# Secondary_Protection.net
KiCad netlist of a schematic drawn in Altium Designer
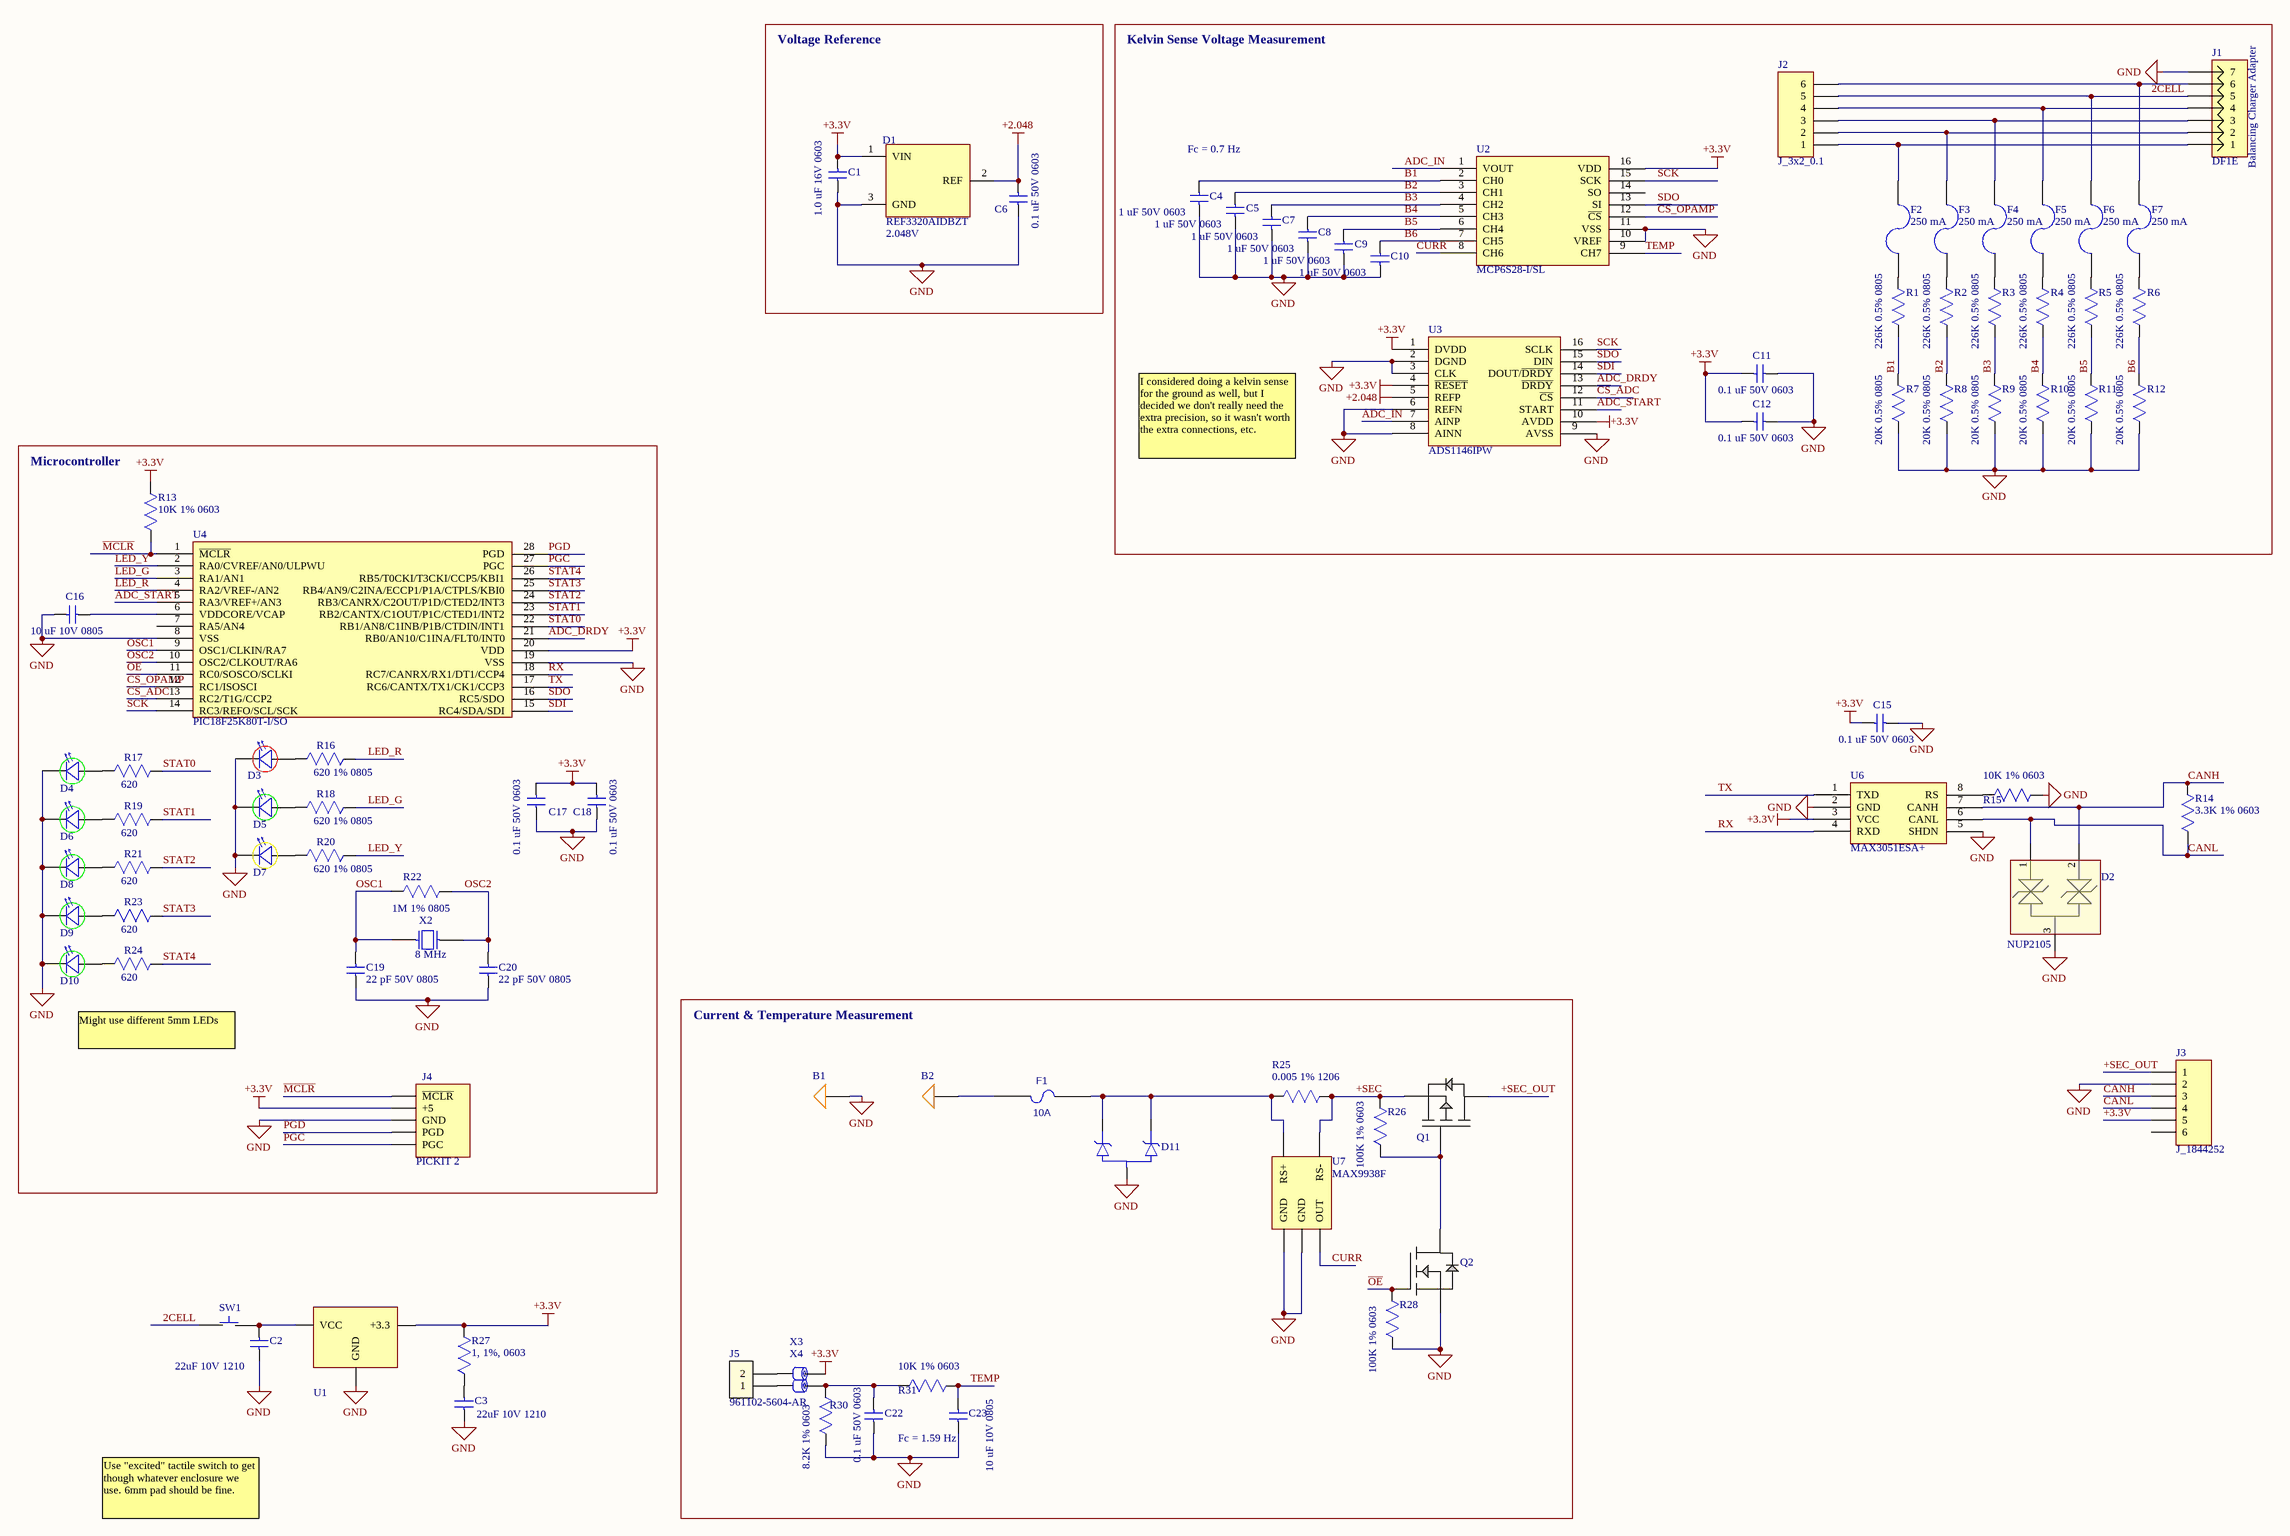
[diagram p0: Secondary Protection.SchDoc]

(export (version "E")
  (design (tool "Eeschema 10.0.6"))
  (components
    (comp (ref "B1")
      (value "J_C3_BATTERY_PAD")
      (footprint "BatteryPad")
      (libsource (lib "c3_SchLib") (part "J_C3_BATTERY_PAD"))
    )
    (comp (ref "B2")
      (value "J_C3_BATTERY_PAD")
      (footprint "BatteryPad")
      (libsource (lib "c3_SchLib") (part "J_C3_BATTERY_PAD"))
    )
    (comp (ref "C1")
      (value "1.0 uF 16V 0603")
      (footprint "0603_cap")
      (description "CAP CER 1UF 16V 10% X7R 0603")
      (fields (field (name "MANUFACTURER") "Taiyo Yuden") (field (name "Comment") "CAP 0603"))
      (libsource (lib "Nutz") (part "C_0603"))
    )
    (comp (ref "C2")
      (value "22uF 10V 1210")
      (footprint "1210_Capacitor")
      (description "CAP CER 22UF 10V 10% X7R 1210")
      (fields (field (name "MANUFACTURER") "TDK Corporation") (field (name "Comment") "CAP 1210"))
      (libsource (lib "c3_SchLib") (part "C_1210"))
    )
    (comp (ref "C3")
      (value "22uF 10V 1210")
      (footprint "1210_Capacitor")
      (description "CAP CER 22UF 10V 10% X7R 1210")
      (fields (field (name "MANUFACTURER") "TDK Corporation") (field (name "Comment") "CAP 1210"))
      (libsource (lib "c3_SchLib") (part "C_1210"))
    )
    (comp (ref "C4")
      (value "1 uF 50V 0603")
      (footprint "0603_cap")
      (description "CAP CER 1UF 50V 10% X7R 0603")
      (fields (field (name "Comment") "CAP 0603"))
      (libsource (lib "Nutz") (part "C_0603"))
    )
    (comp (ref "C5")
      (value "1 uF 50V 0603")
      (footprint "0603_cap")
      (description "CAP CER 1UF 50V 10% X7R 0603")
      (fields (field (name "Comment") "CAP 0603"))
      (libsource (lib "Nutz") (part "C_0603"))
    )
    (comp (ref "C6")
      (value "0.1 uF 50V 0603")
      (footprint "0603_cap")
      (description "CAP CER 0.1UF 50V 10% X7R 0603")
      (fields (field (name "MANUFACTURER") "Yaego") (field (name "Comment") "CAP 0603"))
      (libsource (lib "Nutz") (part "C_0603"))
    )
    (comp (ref "C7")
      (value "1 uF 50V 0603")
      (footprint "0603_cap")
      (description "CAP CER 1UF 50V 10% X7R 0603")
      (fields (field (name "Comment") "CAP 0603"))
      (libsource (lib "Nutz") (part "C_0603"))
    )
    (comp (ref "C8")
      (value "1 uF 50V 0603")
      (footprint "0603_cap")
      (description "CAP CER 1UF 50V 10% X7R 0603")
      (fields (field (name "Comment") "CAP 0603"))
      (libsource (lib "Nutz") (part "C_0603"))
    )
    (comp (ref "C9")
      (value "1 uF 50V 0603")
      (footprint "0603_cap")
      (description "CAP CER 1UF 50V 10% X7R 0603")
      (fields (field (name "Comment") "CAP 0603"))
      (libsource (lib "Nutz") (part "C_0603"))
    )
    (comp (ref "C10")
      (value "1 uF 50V 0603")
      (footprint "0603_cap")
      (description "CAP CER 1UF 50V 10% X7R 0603")
      (fields (field (name "Comment") "CAP 0603"))
      (libsource (lib "Nutz") (part "C_0603"))
    )
    (comp (ref "C11")
      (value "0.1 uF 50V 0603")
      (footprint "0603_cap")
      (description "CAP CER 0.1UF 50V 10% X7R 0603")
      (fields (field (name "MANUFACTURER") "Yaego") (field (name "Comment") "CAP 0603"))
      (libsource (lib "Nutz") (part "C_0603"))
    )
    (comp (ref "C12")
      (value "0.1 uF 50V 0603")
      (footprint "0603_cap")
      (description "CAP CER 0.1UF 50V 10% X7R 0603")
      (fields (field (name "MANUFACTURER") "Yaego") (field (name "Comment") "CAP 0603"))
      (libsource (lib "Nutz") (part "C_0603"))
    )
    (comp (ref "C15")
      (value "0.1 uF 50V 0603")
      (footprint "0603_cap")
      (description "CAP CER 0.1UF 50V 10% X7R 0603")
      (fields (field (name "MANUFACTURER") "Yaego") (field (name "Comment") "CAP 0603"))
      (libsource (lib "Nutz") (part "C_0603"))
    )
    (comp (ref "C16")
      (value "10 uF 10V 0805")
      (footprint "0805_Capacitor")
      (description "CAP CER 10UF 10V 10% X5R 0805")
      (fields (field (name "MANUFACTURER") "Taiyo Yuden") (field (name "Comment") "CAP 0805"))
      (libsource (lib "Nutz") (part "C_0805"))
    )
    (comp (ref "C17")
      (value "0.1 uF 50V 0603")
      (footprint "0603_cap")
      (description "CAP CER 0.1UF 50V 10% X7R 0603")
      (fields (field (name "MANUFACTURER") "Yaego") (field (name "Comment") "CAP 0603"))
      (libsource (lib "Nutz") (part "C_0603"))
    )
    (comp (ref "C18")
      (value "0.1 uF 50V 0603")
      (footprint "0603_cap")
      (description "CAP CER 0.1UF 50V 10% X7R 0603")
      (fields (field (name "MANUFACTURER") "Yaego") (field (name "Comment") "CAP 0603"))
      (libsource (lib "Nutz") (part "C_0603"))
    )
    (comp (ref "C19")
      (value "22 pF 50V 0805")
      (footprint "0805_Capacitor")
      (description "CAP CER 22PF 50V 5% NP0 0805")
      (fields (field (name "MANUFACTURER") "Johanson Dielectrics Inc") (field (name "Comment") "CAP 0805"))
      (libsource (lib "Nutz") (part "C_0805"))
    )
    (comp (ref "C20")
      (value "22 pF 50V 0805")
      (footprint "0805_Capacitor")
      (description "CAP CER 22PF 50V 5% NP0 0805")
      (fields (field (name "MANUFACTURER") "Johanson Dielectrics Inc") (field (name "Comment") "CAP 0805"))
      (libsource (lib "Nutz") (part "C_0805"))
    )
    (comp (ref "C22")
      (value "0.1 uF 50V 0603")
      (footprint "0603_cap")
      (description "CAP CER 0.1UF 50V 10% X7R 0603")
      (fields (field (name "MANUFACTURER") "Yaego") (field (name "Comment") "CAP 0603"))
      (libsource (lib "Nutz") (part "C_0603"))
    )
    (comp (ref "C23")
      (value "10 uF 10V 0805")
      (footprint "0805_Capacitor")
      (description "CAP CER 10UF 10V 10% X5R 0805")
      (fields (field (name "MANUFACTURER") "Taiyo Yuden") (field (name "Comment") "CAP 0805"))
      (libsource (lib "Nutz") (part "C_0805"))
    )
    (comp (ref "D1")
      (value "2.048V")
      (footprint "SOT-23")
      (description "IC LDO V-REF 2.048V SOT23-3")
      (fields (field (name "MANUFACTURER") "TI") (field (name "MANUFACTURER PN") "REF3320AIDBZT"))
      (libsource (lib "c3_SchLib") (part "D_REF3320AIDBZT"))
    )
    (comp (ref "D2")
      (value "CAN TVS")
      (footprint "SOT-23")
      (description "IC CAN BUS PROTECTOR DUAL SOT23")
      (fields (field (name "MANUFACTURER") "ON Semiconductor") (field (name "MANUFACTURER PN") "NUP2105"))
      (libsource (lib "c3_SchLib") (part "D_NUP2105"))
    )
    (comp (ref "D3")
      (value "D_LED_0805_RED")
      (footprint "0805P_RED")
      (description "LED 2X1.2MM 625NM RD WTR CLR SMD 0805")
      (fields (field (name "MANUFACTURER") "Kingbright Corp"))
      (libsource (lib "c3_SchLib") (part "D_LED_0805_RED"))
    )
    (comp (ref "D4")
      (value "D_LED_5MM_GREEN")
      (footprint "LED_5mm_GREEN")
      (description "LED 5MM GREEN CLEAR 527NM 15DEG")
      (fields (field (name "MANUFACTURER") "Cree Inc") (field (name "SVP CREATOR") "Matt Crane"))
      (libsource (lib "c3_SchLib") (part "D_LED_5MM_GREEN"))
    )
    (comp (ref "D5")
      (value "D_LED_0805_GREEN")
      (footprint "0805P_Green")
      (description "LED 2X1.2MM 568NM GN WTR CLR SMD 0805")
      (fields (field (name "MANUFACTURER") "Kingbright Corp"))
      (libsource (lib "c3_SchLib") (part "D_LED_0805_GREEN"))
    )
    (comp (ref "D6")
      (value "D_LED_5MM_GREEN")
      (footprint "LED_5mm_GREEN")
      (description "LED 5MM GREEN CLEAR 527NM 15DEG")
      (fields (field (name "MANUFACTURER") "Cree Inc") (field (name "SVP CREATOR") "Matt Crane"))
      (libsource (lib "c3_SchLib") (part "D_LED_5MM_GREEN"))
    )
    (comp (ref "D7")
      (value "D_LED_0805_YELLOW")
      (footprint "0805P_YELLOW")
      (description "LED 2X1.2MM 588NM YW WTR CLR SMD 0805")
      (fields (field (name "MANUFACTURER") "Kingbright Corp"))
      (libsource (lib "c3_SchLib") (part "D_LED_0805_YELLOW"))
    )
    (comp (ref "D8")
      (value "D_LED_5MM_GREEN")
      (footprint "LED_5mm_GREEN")
      (description "LED 5MM GREEN CLEAR 527NM 15DEG")
      (fields (field (name "MANUFACTURER") "Cree Inc") (field (name "SVP CREATOR") "Matt Crane"))
      (libsource (lib "c3_SchLib") (part "D_LED_5MM_GREEN"))
    )
    (comp (ref "D9")
      (value "D_LED_5MM_GREEN")
      (footprint "LED_5mm_GREEN")
      (description "LED 5MM GREEN CLEAR 527NM 15DEG")
      (fields (field (name "MANUFACTURER") "Cree Inc") (field (name "SVP CREATOR") "Matt Crane"))
      (libsource (lib "c3_SchLib") (part "D_LED_5MM_GREEN"))
    )
    (comp (ref "D10")
      (value "D_LED_5MM_GREEN")
      (footprint "LED_5mm_GREEN")
      (description "LED 5MM GREEN CLEAR 527NM 15DEG")
      (fields (field (name "MANUFACTURER") "Cree Inc") (field (name "SVP CREATOR") "Matt Crane"))
      (libsource (lib "c3_SchLib") (part "D_LED_5MM_GREEN"))
    )
    (comp (ref "D11")
      (value "D_AZ23C36-TP")
      (footprint "SOT-23")
      (description "DIODE ZENER DUAL 36V SOT-23")
      (fields (field (name "MANUFACTURER") "Micro") (field (name "SVP CREATOR") "Jonathan Nutzmann"))
      (libsource (lib "c3_SchLib") (part "D_AZ23C36-TP"))
    )
    (comp (ref "F1")
      (value "10A")
      (footprint "FUSEHOLDER - AutoBlade")
      (description "FUSE HOLDER ATO AUTO BLADE")
      (fields (field (name "PART NUMBER") "3550-2") (field (name "MANUFACTURER") "KEYSTONE/EQUIV."))
      (libsource (lib "G_discrt") (part "FUSEHOLDER AutoBlade"))
    )
    (comp (ref "F2")
      (value "250 mA")
      (footprint "1206_RESISTOR")
      (description "FUSE 250 mA 1206")
      (fields (field (name "SVN CREATOR") "Jonathan Nutzmann") (field (name "SVN REVIEWER 2") "*"))
      (libsource (lib "c3_SchLib") (part "F_250mA_1206"))
    )
    (comp (ref "F3")
      (value "250 mA")
      (footprint "1206_RESISTOR")
      (description "FUSE 250 mA 1206")
      (fields (field (name "SVN CREATOR") "Jonathan Nutzmann") (field (name "SVN REVIEWER 2") "*"))
      (libsource (lib "c3_SchLib") (part "F_250mA_1206"))
    )
    (comp (ref "F4")
      (value "250 mA")
      (footprint "1206_RESISTOR")
      (description "FUSE 250 mA 1206")
      (fields (field (name "SVN CREATOR") "Jonathan Nutzmann") (field (name "SVN REVIEWER 2") "*"))
      (libsource (lib "c3_SchLib") (part "F_250mA_1206"))
    )
    (comp (ref "F5")
      (value "250 mA")
      (footprint "1206_RESISTOR")
      (description "FUSE 250 mA 1206")
      (fields (field (name "SVN CREATOR") "Jonathan Nutzmann") (field (name "SVN REVIEWER 2") "*"))
      (libsource (lib "c3_SchLib") (part "F_250mA_1206"))
    )
    (comp (ref "F6")
      (value "250 mA")
      (footprint "1206_RESISTOR")
      (description "FUSE 250 mA 1206")
      (fields (field (name "SVN CREATOR") "Jonathan Nutzmann") (field (name "SVN REVIEWER 2") "*"))
      (libsource (lib "c3_SchLib") (part "F_250mA_1206"))
    )
    (comp (ref "F7")
      (value "250 mA")
      (footprint "1206_RESISTOR")
      (description "FUSE 250 mA 1206")
      (fields (field (name "SVN CREATOR") "Jonathan Nutzmann") (field (name "SVN REVIEWER 2") "*"))
      (libsource (lib "c3_SchLib") (part "F_250mA_1206"))
    )
    (comp (ref "J1")
      (value "DF1E")
      (footprint "DF1EC-7P-2.5DSA")
      (description "7-pin Hirose")
      (fields
        (field (name "MANUFACTURER") "Hirose Electric Co Ltd")
        (field (name "Comment") "DF1E 5-pin Male Header")
        (field (name "SVP CREATOR") "Adam Shea")
      )
      (libsource (lib "Hirose") (part "DF1E_7_S"))
    )
    (comp (ref "J2")
      (value "J_3x2_0.1")
      (footprint "6PIN_2_.100IN")
      (description "3 x 2 0.1\" Header")
      (libsource (lib "Nutz") (part "J_3x2_0.1"))
    )
    (comp (ref "J3")
      (value "J_1844252")
      (footprint "1844252")
      (description "CONN HEADER RT ANG 6POS 3.5MM")
      (fields (field (name "MANUFACTURER") "Phoenix Contact"))
      (libsource (lib "Nutz") (part "J_1803316"))
    )
    (comp (ref "J4")
      (value "PICKIT 2")
      (footprint "CONN FEMALE 5POS .100\" R/A GOLD")
      (description "PICKIT2 PROG HEADER")
      (fields
        (field (name "MANUFACTURER") "Sullins Connector Solutions")
        (field (name "Comment") "J_PICKIT2_5")
      )
      (libsource (lib "c3_SchLib") (part "J_PICKIT2_5"))
    )
    (comp (ref "J5")
      (value "J_Thermistor_Connector")
      (footprint "SIP_HEADER_2")
      (description "Thermistor Connector")
      (fields (field (name "MANUFACTURER PN") "961102-5604-AR") (field (name "MANUFACTURER") "3M"))
      (libsource (lib "c3_SchLib") (part "J_Thermistor_Connector"))
    )
    (comp (ref "Q1")
      (value "MOSFET P-CH 30V 25A TO-252")
      (footprint "DPAK")
      (description "MOSFET P-CH 30V 25A TO-252 DPAK")
      (fields
        (field (name "MANUFACTURER") "Alpha & Omega Semiconductor Inc")
        (field (name "SVP CREATOR") "Brittany Pentek")
        (field (name "SVP REVIEWER 1") "Brett Paulsen")
      )
      (libsource (lib "c3_SchLib") (part "Q_AOD417_ P-CH_-30A_-25A_DPAK"))
    )
    (comp (ref "Q2")
      (value "RK7002BT116")
      (footprint "SOT-23")
      (description "MOSFET N-CH 60V 250MA SOT-23")
      (fields
        (field (name "MANUFACTURER") "Rohm Semiconductor")
        (field (name "SVP CREATOR") "Jonathan Nutzmann")
      )
      (libsource (lib "c3_SchLib") (part "Q_N_60V_250MA_SOT23"))
    )
    (comp (ref "R1")
      (value "226K 0.5% 0805")
      (footprint "0805_Resistor")
      (description "RESISTOR, 1/10W, 226K, 0.5%, 0805")
      (fields (field (name "MANUFACTURER") "Susumu") (field (name "Comment") "RES 0805"))
      (libsource (lib "Nutz") (part "R_0805"))
    )
    (comp (ref "R2")
      (value "226K 0.5% 0805")
      (footprint "0805_Resistor")
      (description "RESISTOR, 1/10W, 226K, 0.5%, 0805")
      (fields (field (name "MANUFACTURER") "Susumu") (field (name "Comment") "RES 0805"))
      (libsource (lib "Nutz") (part "R_0805"))
    )
    (comp (ref "R3")
      (value "226K 0.5% 0805")
      (footprint "0805_Resistor")
      (description "RESISTOR, 1/10W, 226K, 0.5%, 0805")
      (fields (field (name "MANUFACTURER") "Susumu") (field (name "Comment") "RES 0805"))
      (libsource (lib "Nutz") (part "R_0805"))
    )
    (comp (ref "R4")
      (value "226K 0.5% 0805")
      (footprint "0805_Resistor")
      (description "RESISTOR, 1/10W, 226K, 0.5%, 0805")
      (fields (field (name "MANUFACTURER") "Susumu") (field (name "Comment") "RES 0805"))
      (libsource (lib "Nutz") (part "R_0805"))
    )
    (comp (ref "R5")
      (value "226K 0.5% 0805")
      (footprint "0805_Resistor")
      (description "RESISTOR, 1/10W, 226K, 0.5%, 0805")
      (fields (field (name "MANUFACTURER") "Susumu") (field (name "Comment") "RES 0805"))
      (libsource (lib "Nutz") (part "R_0805"))
    )
    (comp (ref "R6")
      (value "226K 0.5% 0805")
      (footprint "0805_Resistor")
      (description "RESISTOR, 1/10W, 226K, 0.5%, 0805")
      (fields (field (name "MANUFACTURER") "Susumu") (field (name "Comment") "RES 0805"))
      (libsource (lib "Nutz") (part "R_0805"))
    )
    (comp (ref "R7")
      (value "20K 0.5% 0805")
      (footprint "0805_Resistor")
      (description "RESISTOR, 1/10W, 20K, 0.5%, 0805")
      (fields (field (name "MANUFACTURER") "Susumu") (field (name "Comment") "RES 0805"))
      (libsource (lib "Nutz") (part "R_0805"))
    )
    (comp (ref "R8")
      (value "20K 0.5% 0805")
      (footprint "0805_Resistor")
      (description "RESISTOR, 1/10W, 20K, 0.5%, 0805")
      (fields (field (name "MANUFACTURER") "Susumu") (field (name "Comment") "RES 0805"))
      (libsource (lib "Nutz") (part "R_0805"))
    )
    (comp (ref "R9")
      (value "20K 0.5% 0805")
      (footprint "0805_Resistor")
      (description "RESISTOR, 1/10W, 20K, 0.5%, 0805")
      (fields (field (name "MANUFACTURER") "Susumu") (field (name "Comment") "RES 0805"))
      (libsource (lib "Nutz") (part "R_0805"))
    )
    (comp (ref "R10")
      (value "20K 0.5% 0805")
      (footprint "0805_Resistor")
      (description "RESISTOR, 1/10W, 20K, 0.5%, 0805")
      (fields (field (name "MANUFACTURER") "Susumu") (field (name "Comment") "RES 0805"))
      (libsource (lib "Nutz") (part "R_0805"))
    )
    (comp (ref "R11")
      (value "20K 0.5% 0805")
      (footprint "0805_Resistor")
      (description "RESISTOR, 1/10W, 20K, 0.5%, 0805")
      (fields (field (name "MANUFACTURER") "Susumu") (field (name "Comment") "RES 0805"))
      (libsource (lib "Nutz") (part "R_0805"))
    )
    (comp (ref "R12")
      (value "20K 0.5% 0805")
      (footprint "0805_Resistor")
      (description "RESISTOR, 1/10W, 20K, 0.5%, 0805")
      (fields (field (name "MANUFACTURER") "Susumu") (field (name "Comment") "RES 0805"))
      (libsource (lib "Nutz") (part "R_0805"))
    )
    (comp (ref "R13")
      (value "10K 1% 0603")
      (footprint "0603_res")
      (description "RESISTOR, 1/10W, 10K, 1%, 0603")
      (fields (field (name "MANUFACTURER") "ANY / EQUIV") (field (name "Comment") "RES 0603"))
      (libsource (lib "Nutz") (part "R_0603"))
    )
    (comp (ref "R14")
      (value "3.3K 1% 0603")
      (footprint "0603_res")
      (description "RESISTOR, 1/10W, 3.3K, 1%, 0603")
      (fields (field (name "MANUFACTURER") "ANY / EQUIV") (field (name "Comment") "RES 0603"))
      (libsource (lib "Nutz") (part "R_0603"))
    )
    (comp (ref "R15")
      (value "10K 1% 0603")
      (footprint "0603_res")
      (description "RESISTOR, 1/10W, 10K, 1%, 0603")
      (fields (field (name "MANUFACTURER") "ANY / EQUIV") (field (name "Comment") "RES 0603"))
      (libsource (lib "Nutz") (part "R_0603"))
    )
    (comp (ref "R16")
      (value "620 1% 0805")
      (footprint "0805_Resistor")
      (description "RESISTOR, 1/8W, 620, 1%, 0805")
      (fields (field (name "MANUFACTURER") "ANY / EQUIV") (field (name "Comment") "R_0805_620_1%"))
      (libsource (lib "c3_SchLib") (part "R_0805_620_1%"))
    )
    (comp (ref "R17")
      (value "620")
      (footprint "0805_Resistor")
      (description "RES 620 OHM 1/8W 1% 0805 SMD")
      (fields (field (name "Comment") "R_0805_620_1%") (field (name "SVP CREATOR") "Jonathan Nutzmann"))
      (libsource (lib "c3_SchLib") (part "R_0805_620_1%"))
    )
    (comp (ref "R18")
      (value "620 1% 0805")
      (footprint "0805_Resistor")
      (description "RESISTOR, 1/8W, 620, 1%, 0805")
      (fields (field (name "MANUFACTURER") "ANY / EQUIV") (field (name "Comment") "R_0805_620_1%"))
      (libsource (lib "c3_SchLib") (part "R_0805_620_1%"))
    )
    (comp (ref "R19")
      (value "620")
      (footprint "0805_Resistor")
      (description "RES 620 OHM 1/8W 1% 0805 SMD")
      (fields (field (name "Comment") "R_0805_620_1%") (field (name "SVP CREATOR") "Jonathan Nutzmann"))
      (libsource (lib "c3_SchLib") (part "R_0805_620_1%"))
    )
    (comp (ref "R20")
      (value "620 1% 0805")
      (footprint "0805_Resistor")
      (description "RESISTOR, 1/8W, 620, 1%, 0805")
      (fields (field (name "MANUFACTURER") "ANY / EQUIV") (field (name "Comment") "R_0805_620_1%"))
      (libsource (lib "c3_SchLib") (part "R_0805_620_1%"))
    )
    (comp (ref "R21")
      (value "620")
      (footprint "0805_Resistor")
      (description "RES 620 OHM 1/8W 1% 0805 SMD")
      (fields (field (name "Comment") "R_0805_620_1%") (field (name "SVP CREATOR") "Jonathan Nutzmann"))
      (libsource (lib "c3_SchLib") (part "R_0805_620_1%"))
    )
    (comp (ref "R22")
      (value "1M 1% 0805")
      (footprint "0805_Resistor")
      (description "RESISTOR, 1/8W, 1M, 1%, 0805")
      (fields (field (name "MANUFACTURER") "ANY / EQUIV") (field (name "Comment") "RES 0805"))
      (libsource (lib "Nutz") (part "R_0805"))
    )
    (comp (ref "R23")
      (value "620")
      (footprint "0805_Resistor")
      (description "RES 620 OHM 1/8W 1% 0805 SMD")
      (fields (field (name "Comment") "R_0805_620_1%") (field (name "SVP CREATOR") "Jonathan Nutzmann"))
      (libsource (lib "c3_SchLib") (part "R_0805_620_1%"))
    )
    (comp (ref "R24")
      (value "620")
      (footprint "0805_Resistor")
      (description "RES 620 OHM 1/8W 1% 0805 SMD")
      (fields (field (name "Comment") "R_0805_620_1%") (field (name "SVP CREATOR") "Jonathan Nutzmann"))
      (libsource (lib "c3_SchLib") (part "R_0805_620_1%"))
    )
    (comp (ref "R25")
      (value "0.005 1% 1206")
      (footprint "1206_Resistor")
      (description "RES CURRENT SENSE .005 OHM 1W 1%")
      (fields (field (name "MANUFACTURER") "MCS1632R010FER") (field (name "Comment") "R_0805_0.01_1%"))
      (libsource (lib "c3_SchLib") (part "R_0805_0.01_1%"))
    )
    (comp (ref "R26")
      (value "100K 1% 0603")
      (footprint "0603_res")
      (description "RESISTOR, 1/10W, 500K, 1%, 0603")
      (fields (field (name "MANUFACTURER") "ANY / EQUIV") (field (name "Comment") "RES 0603"))
      (libsource (lib "Nutz") (part "R_0603"))
    )
    (comp (ref "R27")
      (value "1, 1%, 0603")
      (footprint "0603_res")
      (description "RES 0603")
      (libsource (lib "Nutz") (part "R_0603"))
    )
    (comp (ref "R28")
      (value "100K 1% 0603")
      (footprint "0603_res")
      (description "RESISTOR, 1/10W, 500K, 1%, 0603")
      (fields (field (name "MANUFACTURER") "ANY / EQUIV") (field (name "Comment") "RES 0603"))
      (libsource (lib "Nutz") (part "R_0603"))
    )
    (comp (ref "R30")
      (value "8.2K 1% 0603")
      (footprint "0603_res")
      (description "RESISTOR, 1/10W, 8.2K, 1%, 0603")
      (fields (field (name "MANUFACTURER") "ANY / EQUIV") (field (name "Comment") "RES 0603"))
      (libsource (lib "Nutz") (part "R_0603"))
    )
    (comp (ref "R31")
      (value "10K 1% 0603")
      (footprint "0603_res")
      (description "RESISTOR, 1/10W, 10K, 1%, 0603")
      (fields (field (name "MANUFACTURER") "ANY / EQUIV") (field (name "Comment") "RES 0603"))
      (libsource (lib "Nutz") (part "R_0603"))
    )
    (comp (ref "SW1")
      (value "SW_TACT_SWITCH_6x6")
      (footprint "TACT_SWITCH_6x6")
      (description "SWITCH TACT 6MM BLACK 160GF")
      (fields (field (name "MANUFACTURER") "Tyco Electronics") (field (name "SVP CREATOR") "Nate Bolyard"))
      (libsource (lib "Noprotection") (part "SW_TACT_SWITCH_6x6"))
    )
    (comp (ref "U1")
      (value "MC7805BDTG")
      (footprint "DPAK")
      (description "IC REG LDO BIPO 1A 3.3V TO252-3")
      (fields (field (name "MANUFACTURER") "Diodes Inc") (field (name "SVP CREATOR") "Thomas Daede"))
      (libsource (lib "c3_SchLib") (part "U_AP1117D33G_1"))
    )
    (comp (ref "U2")
      (value "U_MCP6S28-I/SL")
      (footprint "SOIC127P600X175-16N")
      (description "IC PGA 8CH R-R I/O 16SOIC")
      (fields (field (name "MANUFACTURER") "Microchip") (field (name "MANUFACTURER PN") "MCP6S28-I/SL"))
      (libsource (lib "Nutz") (part "U_MCP6S28-I/SL"))
    )
    (comp (ref "U3")
      (value "U_ADS1146IPW")
      (footprint "ADS1146IPW")
      (description "IC ADC 16BIT SRL 2KSPS 16TSSOP")
      (fields (field (name "MANUFACTURER") "Texas Instruments") (field (name "MANUFACTURER PN") "ADS1146IPW"))
      (libsource (lib "Nutz") (part "U_ADS1146IPW"))
    )
    (comp (ref "U4")
      (value "PIC18F25K80")
      (footprint "SOIC127P1030X265-28N")
      (description "MCU PIC 32KB FLASH 28SOIC")
      (fields (field (name "MANUFACTURER") "Microchip") (field (name "MANUFACTURER PN") "PIC18F25K80T-I/SO"))
      (libsource (lib "c3_SchLib") (part "U_PIC18F25K80"))
    )
    (comp (ref "U6")
      (value "U_MAX3051")
      (footprint "SOIC127P600X175-8N")
      (description "IC TXRX CAN 1MBPS 8-SOIC 3.3V")
      (fields (field (name "MANUFACTURER") "Maxim") (field (name "MANUFACTURER PN") "MAX3051ESA+"))
      (libsource (lib "c3_SchLib") (part "U_MAX3051"))
    )
    (comp (ref "U7")
      (value "MAX9938F")
      (footprint "SOT95P280X145-5N")
      (description "IC AMP CURRENT SENSE SOT23-5")
      (fields (field (name "MANUFACTURER") "Maxim") (field (name "Comment") "U_ MAX9938F"))
      (libsource (lib "c3_SchLib") (part "U_ MAX9938F"))
    )
    (comp (ref "X2")
      (value "8 MHz")
      (footprint "HC-49")
      (description "CRYSTAL 8.00 MHZ 20PF 49US")
      (fields (field (name "MANUFACTURER") "ECS") (field (name "Comment") "HC49"))
      (libsource (lib "c3_SchLib") (part "X_HC49"))
    )
    (comp (ref "X3")
      (value "0603")
      (footprint "0603_res")
      (description "FERRITE CHIP 2A 300 OHM SMD")
      (fields (field (name "MANUFACTURER") "Laird-Signal Integrity Products"))
      (libsource (lib "Nutz") (part "X_0603_FERRITE"))
    )
    (comp (ref "X4")
      (value "0603")
      (footprint "0603_res")
      (description "FERRITE CHIP 2A 300 OHM SMD")
      (fields (field (name "MANUFACTURER") "Laird-Signal Integrity Products"))
      (libsource (lib "Nutz") (part "X_0603_FERRITE"))
    )
  )
  (nets
    (net (code "1") (name "+2.048") (class "Default")
      (node (ref "C6") (pin "1") (pinfunction "1_1") (pintype "passive"))
      (node (ref "D1") (pin "2") (pinfunction "REF_2") (pintype "passive"))
      (node (ref "U3") (pin "5") (pinfunction "REFP_5") (pintype "passive"))
    )
    (net (code "2") (name "+3.3V") (class "Default")
      (node (ref "C1") (pin "1") (pinfunction "1_1") (pintype "passive"))
      (node (ref "C11") (pin "2") (pinfunction "2_2") (pintype "passive"))
      (node (ref "C12") (pin "2") (pinfunction "2_2") (pintype "passive"))
      (node (ref "C15") (pin "1") (pinfunction "1_1") (pintype "passive"))
      (node (ref "C17") (pin "1") (pinfunction "1_1") (pintype "passive"))
      (node (ref "C18") (pin "1") (pinfunction "1_1") (pintype "passive"))
      (node (ref "D1") (pin "1") (pinfunction "VIN_1") (pintype "passive"))
      (node (ref "J3") (pin "5") (pinfunction "5_5") (pintype "passive"))
      (node (ref "J4") (pin "+5") (pinfunction "+5_+5") (pintype "passive"))
      (node (ref "R13") (pin "1") (pinfunction "1_1") (pintype "passive"))
      (node (ref "R27") (pin "1") (pinfunction "1_1") (pintype "passive"))
      (node (ref "U1") (pin "1") (pinfunction "+3.3_1") (pintype "passive"))
      (node (ref "U2") (pin "16") (pinfunction "VDD_16") (pintype "passive"))
      (node (ref "U3") (pin "1") (pinfunction "DVDD_1") (pintype "passive"))
      (node (ref "U3") (pin "10") (pinfunction "AVDD_10") (pintype "passive"))
      (node (ref "U3") (pin "4") (pinfunction "~{RESET}_4") (pintype "passive"))
      (node (ref "U4") (pin "20") (pinfunction "VDD_20") (pintype "passive"))
      (node (ref "U6") (pin "3") (pinfunction "VCC_3") (pintype "passive"))
      (node (ref "X3") (pin "2") (pinfunction "2_2") (pintype "passive"))
    )
    (net (code "3") (name "/+SEC") (class "Default")
      (node (ref "Q1") (pin "2") (pinfunction "SOURCE_2") (pintype "passive"))
      (node (ref "R25") (pin "1") (pinfunction "1_1") (pintype "passive"))
      (node (ref "R26") (pin "1") (pinfunction "1_1") (pintype "passive"))
      (node (ref "U7") (pin "4") (pinfunction "RS-_4") (pintype "passive"))
    )
    (net (code "4") (name "/+SEC_OUT") (class "Default")
      (node (ref "J3") (pin "1") (pinfunction "1_1") (pintype "passive"))
      (node (ref "Q1") (pin "1") (pinfunction "DRAIN_1") (pintype "passive"))
    )
    (net (code "5") (name "/2CELL") (class "Default")
      (node (ref "F6") (pin "2") (pinfunction "2_2") (pintype "passive"))
      (node (ref "J1") (pin "5") (pinfunction "5_5") (pintype "passive"))
      (node (ref "J2") (pin "5") (pinfunction "5_5") (pintype "passive"))
      (node (ref "SW1") (pin "1") (pinfunction "1_1") (pintype "passive"))
    )
    (net (code "6") (name "/ADC_DRDY") (class "Default")
      (node (ref "U3") (pin "13") (pinfunction "~{DRDY}_13") (pintype "passive"))
      (node (ref "U4") (pin "21") (pinfunction "RB0/AN10/C1INA/FLT0/INT0_21") (pintype "passive"))
    )
    (net (code "7") (name "/ADC_IN") (class "Default")
      (node (ref "U2") (pin "1") (pinfunction "VOUT_1") (pintype "passive"))
      (node (ref "U3") (pin "7") (pinfunction "AINP_7") (pintype "passive"))
    )
    (net (code "8") (name "/ADC_START") (class "Default")
      (node (ref "U3") (pin "11") (pinfunction "START_11") (pintype "passive"))
      (node (ref "U4") (pin "5") (pinfunction "RA3/VREF+/AN3_5") (pintype "passive"))
    )
    (net (code "9") (name "/B1") (class "Default")
      (node (ref "C4") (pin "2") (pinfunction "2_2") (pintype "passive"))
      (node (ref "R1") (pin "2") (pinfunction "2_2") (pintype "passive"))
      (node (ref "R7") (pin "1") (pinfunction "1_1") (pintype "passive"))
      (node (ref "U2") (pin "2") (pinfunction "CH0_2") (pintype "passive"))
    )
    (net (code "10") (name "/B2") (class "Default")
      (node (ref "C5") (pin "2") (pinfunction "2_2") (pintype "passive"))
      (node (ref "R2") (pin "2") (pinfunction "2_2") (pintype "passive"))
      (node (ref "R8") (pin "1") (pinfunction "1_1") (pintype "passive"))
      (node (ref "U2") (pin "3") (pinfunction "CH1_3") (pintype "passive"))
    )
    (net (code "11") (name "/B3") (class "Default")
      (node (ref "C7") (pin "2") (pinfunction "2_2") (pintype "passive"))
      (node (ref "R3") (pin "2") (pinfunction "2_2") (pintype "passive"))
      (node (ref "R9") (pin "1") (pinfunction "1_1") (pintype "passive"))
      (node (ref "U2") (pin "4") (pinfunction "CH2_4") (pintype "passive"))
    )
    (net (code "12") (name "/B4") (class "Default")
      (node (ref "C8") (pin "2") (pinfunction "2_2") (pintype "passive"))
      (node (ref "R10") (pin "1") (pinfunction "1_1") (pintype "passive"))
      (node (ref "R4") (pin "2") (pinfunction "2_2") (pintype "passive"))
      (node (ref "U2") (pin "5") (pinfunction "CH3_5") (pintype "passive"))
    )
    (net (code "13") (name "/B5") (class "Default")
      (node (ref "C9") (pin "2") (pinfunction "2_2") (pintype "passive"))
      (node (ref "R11") (pin "1") (pinfunction "1_1") (pintype "passive"))
      (node (ref "R5") (pin "2") (pinfunction "2_2") (pintype "passive"))
      (node (ref "U2") (pin "6") (pinfunction "CH4_6") (pintype "passive"))
    )
    (net (code "14") (name "/B6") (class "Default")
      (node (ref "C10") (pin "2") (pinfunction "2_2") (pintype "passive"))
      (node (ref "R12") (pin "1") (pinfunction "1_1") (pintype "passive"))
      (node (ref "R6") (pin "2") (pinfunction "2_2") (pintype "passive"))
      (node (ref "U2") (pin "7") (pinfunction "CH5_7") (pintype "passive"))
    )
    (net (code "15") (name "/CANH") (class "Default")
      (node (ref "D2") (pin "2") (pintype "passive"))
      (node (ref "J3") (pin "3") (pinfunction "3_3") (pintype "passive"))
      (node (ref "R14") (pin "1") (pinfunction "1_1") (pintype "passive"))
      (node (ref "U6") (pin "7") (pinfunction "CANH_7") (pintype "passive"))
    )
    (net (code "16") (name "/CANL") (class "Default")
      (node (ref "D2") (pin "1") (pintype "passive"))
      (node (ref "J3") (pin "4") (pinfunction "4_4") (pintype "passive"))
      (node (ref "R14") (pin "2") (pinfunction "2_2") (pintype "passive"))
      (node (ref "U6") (pin "6") (pinfunction "CANL_6") (pintype "passive"))
    )
    (net (code "17") (name "/CURR") (class "Default")
      (node (ref "U2") (pin "8") (pinfunction "CH6_8") (pintype "passive"))
      (node (ref "U7") (pin "3") (pinfunction "OUT_3") (pintype "passive"))
    )
    (net (code "18") (name "/LED_G") (class "Default")
      (node (ref "R18") (pin "1") (pinfunction "1_1") (pintype "passive"))
      (node (ref "U4") (pin "3") (pinfunction "RA1/AN1_3") (pintype "passive"))
    )
    (net (code "19") (name "/LED_R") (class "Default")
      (node (ref "R16") (pin "1") (pinfunction "1_1") (pintype "passive"))
      (node (ref "U4") (pin "4") (pinfunction "RA2/VREF-/AN2_4") (pintype "passive"))
    )
    (net (code "20") (name "/LED_Y") (class "Default")
      (node (ref "R20") (pin "1") (pinfunction "1_1") (pintype "passive"))
      (node (ref "U4") (pin "2") (pinfunction "RA0/CVREF/AN0/ULPWU_2") (pintype "passive"))
    )
    (net (code "21") (name "/OSC1") (class "Default")
      (node (ref "C19") (pin "1") (pinfunction "1_1") (pintype "passive"))
      (node (ref "R22") (pin "2") (pinfunction "2_2") (pintype "passive"))
      (node (ref "U4") (pin "9") (pinfunction "OSC1/CLKIN/RA7_9") (pintype "passive"))
      (node (ref "X2") (pin "2") (pinfunction "2_2") (pintype "passive"))
    )
    (net (code "22") (name "/OSC2") (class "Default")
      (node (ref "C20") (pin "1") (pinfunction "1_1") (pintype "passive"))
      (node (ref "R22") (pin "1") (pinfunction "1_1") (pintype "passive"))
      (node (ref "U4") (pin "10") (pinfunction "OSC2/CLKOUT/RA6_10") (pintype "passive"))
      (node (ref "X2") (pin "1") (pinfunction "1_1") (pintype "passive"))
    )
    (net (code "23") (name "/PGC") (class "Default")
      (node (ref "J4") (pin "PGC") (pinfunction "PGC_PGC") (pintype "passive"))
      (node (ref "U4") (pin "27") (pinfunction "PGC_27") (pintype "passive"))
    )
    (net (code "24") (name "/PGD") (class "Default")
      (node (ref "J4") (pin "PGD") (pinfunction "PGD_PGD") (pintype "passive"))
      (node (ref "U4") (pin "28") (pinfunction "PGD_28") (pintype "passive"))
    )
    (net (code "25") (name "/RX") (class "Default")
      (node (ref "U4") (pin "18") (pinfunction "RC7/CANRX/RX1/DT1/CCP4_18") (pintype "passive"))
      (node (ref "U6") (pin "4") (pinfunction "RXD_4") (pintype "passive"))
    )
    (net (code "26") (name "/SCK") (class "Default")
      (node (ref "U2") (pin "15") (pinfunction "SCK_15") (pintype "passive"))
      (node (ref "U3") (pin "16") (pinfunction "SCLK_16") (pintype "passive"))
      (node (ref "U4") (pin "14") (pinfunction "RC3/REFO/SCL/SCK_14") (pintype "passive"))
    )
    (net (code "27") (name "/SDI") (class "Default")
      (node (ref "U3") (pin "14") (pinfunction "DOUT/~{DRDY}_14") (pintype "passive"))
      (node (ref "U4") (pin "15") (pinfunction "RC4/SDA/SDI_15") (pintype "passive"))
    )
    (net (code "28") (name "/SDO") (class "Default")
      (node (ref "U2") (pin "13") (pinfunction "SI_13") (pintype "passive"))
      (node (ref "U3") (pin "15") (pinfunction "DIN_15") (pintype "passive"))
      (node (ref "U4") (pin "16") (pinfunction "RC5/SDO_16") (pintype "passive"))
    )
    (net (code "29") (name "/STAT0") (class "Default")
      (node (ref "R17") (pin "1") (pinfunction "1_1") (pintype "passive"))
      (node (ref "U4") (pin "22") (pinfunction "RB1/AN8/C1INB/P1B/CTDIN/INT1_22") (pintype "passive"))
    )
    (net (code "30") (name "/STAT1") (class "Default")
      (node (ref "R19") (pin "1") (pinfunction "1_1") (pintype "passive"))
      (node (ref "U4") (pin "23") (pinfunction "RB2/CANTX/C1OUT/P1C/CTED1/INT2_23") (pintype "passive"))
    )
    (net (code "31") (name "/STAT2") (class "Default")
      (node (ref "R21") (pin "1") (pinfunction "1_1") (pintype "passive"))
      (node (ref "U4") (pin "24") (pinfunction "RB3/CANRX/C2OUT/P1D/CTED2/INT3_24") (pintype "passive"))
    )
    (net (code "32") (name "/STAT3") (class "Default")
      (node (ref "R23") (pin "1") (pinfunction "1_1") (pintype "passive"))
      (node (ref "U4") (pin "25") (pinfunction "RB4/AN9/C2INA/ECCP1/P1A/CTPLS/KBI0_25") (pintype "passive"))
    )
    (net (code "33") (name "/STAT4") (class "Default")
      (node (ref "R24") (pin "1") (pinfunction "1_1") (pintype "passive"))
      (node (ref "U4") (pin "26") (pinfunction "RB5/T0CKI/T3CKI/CCP5/KBI1_26") (pintype "passive"))
    )
    (net (code "34") (name "/TEMP") (class "Default")
      (node (ref "C23") (pin "1") (pinfunction "1_1") (pintype "passive"))
      (node (ref "R31") (pin "1") (pinfunction "1_1") (pintype "passive"))
      (node (ref "U2") (pin "9") (pinfunction "CH7_9") (pintype "passive"))
    )
    (net (code "35") (name "/TX") (class "Default")
      (node (ref "U4") (pin "17") (pinfunction "RC6/CANTX/TX1/CK1/CCP3_17") (pintype "passive"))
      (node (ref "U6") (pin "1") (pinfunction "TXD_1") (pintype "passive"))
    )
    (net (code "36") (name "/~{CS}_ADC") (class "Default")
      (node (ref "U3") (pin "12") (pinfunction "~{CS}_12") (pintype "passive"))
      (node (ref "U4") (pin "13") (pinfunction "RC2/T1G/CCP2_13") (pintype "passive"))
    )
    (net (code "37") (name "/~{CS}_OPAMP") (class "Default")
      (node (ref "U2") (pin "12") (pinfunction "~{CS}_12") (pintype "passive"))
      (node (ref "U4") (pin "12") (pinfunction "RC1/ISOSCI_12") (pintype "passive"))
    )
    (net (code "38") (name "/~{MCLR}") (class "Default")
      (node (ref "J4") (pin "RST") (pinfunction "~{MCLR}_RST") (pintype "passive"))
      (node (ref "R13") (pin "2") (pinfunction "2_2") (pintype "passive"))
      (node (ref "U4") (pin "1") (pinfunction "~{MCLR}_1") (pintype "passive"))
    )
    (net (code "39") (name "/~{OE}") (class "Default")
      (node (ref "Q2") (pin "1") (pinfunction "GATE_1") (pintype "passive"))
      (node (ref "R28") (pin "1") (pinfunction "1_1") (pintype "passive"))
      (node (ref "U4") (pin "11") (pinfunction "RC0/SOSCO/SCLKI_11") (pintype "passive"))
    )
    (net (code "40") (name "GND") (class "Default")
      (node (ref "B1") (pin "1") (pinfunction "1_1") (pintype "passive"))
      (node (ref "C1") (pin "2") (pinfunction "2_2") (pintype "passive"))
      (node (ref "C10") (pin "1") (pinfunction "1_1") (pintype "passive"))
      (node (ref "C11") (pin "1") (pinfunction "1_1") (pintype "passive"))
      (node (ref "C12") (pin "1") (pinfunction "1_1") (pintype "passive"))
      (node (ref "C15") (pin "2") (pinfunction "2_2") (pintype "passive"))
      (node (ref "C16") (pin "2") (pinfunction "2_2") (pintype "passive"))
      (node (ref "C17") (pin "2") (pinfunction "2_2") (pintype "passive"))
      (node (ref "C18") (pin "2") (pinfunction "2_2") (pintype "passive"))
      (node (ref "C19") (pin "2") (pinfunction "2_2") (pintype "passive"))
      (node (ref "C2") (pin "2") (pinfunction "2_2") (pintype "passive"))
      (node (ref "C20") (pin "2") (pinfunction "2_2") (pintype "passive"))
      (node (ref "C22") (pin "2") (pinfunction "2_2") (pintype "passive"))
      (node (ref "C23") (pin "2") (pinfunction "2_2") (pintype "passive"))
      (node (ref "C3") (pin "2") (pinfunction "2_2") (pintype "passive"))
      (node (ref "C4") (pin "1") (pinfunction "1_1") (pintype "passive"))
      (node (ref "C5") (pin "1") (pinfunction "1_1") (pintype "passive"))
      (node (ref "C6") (pin "2") (pinfunction "2_2") (pintype "passive"))
      (node (ref "C7") (pin "1") (pinfunction "1_1") (pintype "passive"))
      (node (ref "C8") (pin "1") (pinfunction "1_1") (pintype "passive"))
      (node (ref "C9") (pin "1") (pinfunction "1_1") (pintype "passive"))
      (node (ref "D1") (pin "3") (pinfunction "GND_3") (pintype "passive"))
      (node (ref "D10") (pin "1") (pinfunction "Cathode_1") (pintype "passive"))
      (node (ref "D11") (pin "3") (pinfunction "ANODE_3") (pintype "passive"))
      (node (ref "D2") (pin "3") (pintype "passive"))
      (node (ref "D3") (pin "1") (pinfunction "Cathode_1") (pintype "passive"))
      (node (ref "D4") (pin "1") (pinfunction "Cathode_1") (pintype "passive"))
      (node (ref "D5") (pin "1") (pinfunction "Cathode_1") (pintype "passive"))
      (node (ref "D6") (pin "1") (pinfunction "Cathode_1") (pintype "passive"))
      (node (ref "D7") (pin "1") (pinfunction "Cathode_1") (pintype "passive"))
      (node (ref "D8") (pin "1") (pinfunction "Cathode_1") (pintype "passive"))
      (node (ref "D9") (pin "1") (pinfunction "Cathode_1") (pintype "passive"))
      (node (ref "J1") (pin "7") (pinfunction "7_7") (pintype "passive"))
      (node (ref "J3") (pin "2") (pinfunction "2_2") (pintype "passive"))
      (node (ref "J4") (pin "GND") (pinfunction "GND_GND") (pintype "passive"))
      (node (ref "Q2") (pin "2") (pinfunction "SOURCE_2") (pintype "passive"))
      (node (ref "R10") (pin "2") (pinfunction "2_2") (pintype "passive"))
      (node (ref "R11") (pin "2") (pinfunction "2_2") (pintype "passive"))
      (node (ref "R12") (pin "2") (pinfunction "2_2") (pintype "passive"))
      (node (ref "R15") (pin "1") (pinfunction "1_1") (pintype "passive"))
      (node (ref "R28") (pin "2") (pinfunction "2_2") (pintype "passive"))
      (node (ref "R30") (pin "2") (pinfunction "2_2") (pintype "passive"))
      (node (ref "R7") (pin "2") (pinfunction "2_2") (pintype "passive"))
      (node (ref "R8") (pin "2") (pinfunction "2_2") (pintype "passive"))
      (node (ref "R9") (pin "2") (pinfunction "2_2") (pintype "passive"))
      (node (ref "U1") (pin "3") (pinfunction "GND_3") (pintype "passive"))
      (node (ref "U2") (pin "10") (pinfunction "VREF_10") (pintype "passive"))
      (node (ref "U2") (pin "11") (pinfunction "VSS_11") (pintype "passive"))
      (node (ref "U3") (pin "2") (pinfunction "DGND_2") (pintype "passive"))
      (node (ref "U3") (pin "3") (pinfunction "CLK_3") (pintype "passive"))
      (node (ref "U3") (pin "6") (pinfunction "REFN_6") (pintype "passive"))
      (node (ref "U3") (pin "8") (pinfunction "AINN_8") (pintype "passive"))
      (node (ref "U3") (pin "9") (pinfunction "AVSS_9") (pintype "passive"))
      (node (ref "U4") (pin "19") (pinfunction "VSS_19") (pintype "passive"))
      (node (ref "U4") (pin "8") (pinfunction "VSS_8") (pintype "passive"))
      (node (ref "U6") (pin "2") (pinfunction "GND_2") (pintype "passive"))
      (node (ref "U6") (pin "5") (pinfunction "SHDN_5") (pintype "passive"))
      (node (ref "U7") (pin "1") (pinfunction "GND_1") (pintype "passive"))
      (node (ref "U7") (pin "2") (pinfunction "GND_2") (pintype "passive"))
    )
    (net (code "41") (name "Net-(B2-Pad1)") (class "Default")
      (node (ref "B2") (pin "1") (pinfunction "1_1") (pintype "passive"))
      (node (ref "F1") (pin "2") (pintype "passive"))
    )
    (net (code "42") (name "Net-(C3-Pad1)") (class "Default")
      (node (ref "C3") (pin "1") (pinfunction "1_1") (pintype "passive"))
      (node (ref "R27") (pin "2") (pinfunction "2_2") (pintype "passive"))
    )
    (net (code "43") (name "Net-(C22-Pad1)") (class "Default")
      (node (ref "C22") (pin "1") (pinfunction "1_1") (pintype "passive"))
      (node (ref "R30") (pin "1") (pinfunction "1_1") (pintype "passive"))
      (node (ref "R31") (pin "2") (pinfunction "2_2") (pintype "passive"))
      (node (ref "X4") (pin "2") (pinfunction "2_2") (pintype "passive"))
    )
    (net (code "44") (name "Net-(D3-Anode)") (class "Default")
      (node (ref "D3") (pin "2") (pinfunction "Anode_2") (pintype "passive"))
      (node (ref "R16") (pin "2") (pinfunction "2_2") (pintype "passive"))
    )
    (net (code "45") (name "Net-(D4-Anode)") (class "Default")
      (node (ref "D4") (pin "2") (pinfunction "Anode_2") (pintype "passive"))
      (node (ref "R17") (pin "2") (pinfunction "2_2") (pintype "passive"))
    )
    (net (code "46") (name "Net-(D5-Anode)") (class "Default")
      (node (ref "D5") (pin "2") (pinfunction "Anode_2") (pintype "passive"))
      (node (ref "R18") (pin "2") (pinfunction "2_2") (pintype "passive"))
    )
    (net (code "47") (name "Net-(D6-Anode)") (class "Default")
      (node (ref "D6") (pin "2") (pinfunction "Anode_2") (pintype "passive"))
      (node (ref "R19") (pin "2") (pinfunction "2_2") (pintype "passive"))
    )
    (net (code "48") (name "Net-(D7-Anode)") (class "Default")
      (node (ref "D7") (pin "2") (pinfunction "Anode_2") (pintype "passive"))
      (node (ref "R20") (pin "2") (pinfunction "2_2") (pintype "passive"))
    )
    (net (code "49") (name "Net-(D8-Anode)") (class "Default")
      (node (ref "D8") (pin "2") (pinfunction "Anode_2") (pintype "passive"))
      (node (ref "R21") (pin "2") (pinfunction "2_2") (pintype "passive"))
    )
    (net (code "50") (name "Net-(D9-Anode)") (class "Default")
      (node (ref "D9") (pin "2") (pinfunction "Anode_2") (pintype "passive"))
      (node (ref "R23") (pin "2") (pinfunction "2_2") (pintype "passive"))
    )
    (net (code "51") (name "Net-(D10-Anode)") (class "Default")
      (node (ref "D10") (pin "2") (pinfunction "Anode_2") (pintype "passive"))
      (node (ref "R24") (pin "2") (pinfunction "2_2") (pintype "passive"))
    )
    (net (code "52") (name "Net-(D11-CATHODE_1)") (class "Default")
      (node (ref "D11") (pin "1") (pinfunction "CATHODE_1_1") (pintype "passive"))
      (node (ref "D11") (pin "2") (pinfunction "CATHODE_2_2") (pintype "passive"))
      (node (ref "F1") (pin "1") (pintype "passive"))
      (node (ref "R25") (pin "2") (pinfunction "2_2") (pintype "passive"))
      (node (ref "U7") (pin "5") (pinfunction "RS+_5") (pintype "passive"))
    )
    (net (code "53") (name "Net-(F2-Pad1)") (class "Default")
      (node (ref "F2") (pin "1") (pinfunction "1_1") (pintype "passive"))
      (node (ref "R1") (pin "1") (pinfunction "1_1") (pintype "passive"))
    )
    (net (code "54") (name "Net-(F2-Pad2)") (class "Default")
      (node (ref "F2") (pin "2") (pinfunction "2_2") (pintype "passive"))
      (node (ref "J1") (pin "1") (pinfunction "1_1") (pintype "passive"))
      (node (ref "J2") (pin "1") (pinfunction "1_1") (pintype "passive"))
    )
    (net (code "55") (name "Net-(F3-Pad1)") (class "Default")
      (node (ref "F3") (pin "1") (pinfunction "1_1") (pintype "passive"))
      (node (ref "R2") (pin "1") (pinfunction "1_1") (pintype "passive"))
    )
    (net (code "56") (name "Net-(F3-Pad2)") (class "Default")
      (node (ref "F3") (pin "2") (pinfunction "2_2") (pintype "passive"))
      (node (ref "J1") (pin "2") (pinfunction "2_2") (pintype "passive"))
      (node (ref "J2") (pin "2") (pinfunction "2_2") (pintype "passive"))
    )
    (net (code "57") (name "Net-(F4-Pad1)") (class "Default")
      (node (ref "F4") (pin "1") (pinfunction "1_1") (pintype "passive"))
      (node (ref "R3") (pin "1") (pinfunction "1_1") (pintype "passive"))
    )
    (net (code "58") (name "Net-(F4-Pad2)") (class "Default")
      (node (ref "F4") (pin "2") (pinfunction "2_2") (pintype "passive"))
      (node (ref "J1") (pin "3") (pinfunction "3_3") (pintype "passive"))
      (node (ref "J2") (pin "3") (pinfunction "3_3") (pintype "passive"))
    )
    (net (code "59") (name "Net-(F5-Pad1)") (class "Default")
      (node (ref "F5") (pin "1") (pinfunction "1_1") (pintype "passive"))
      (node (ref "R4") (pin "1") (pinfunction "1_1") (pintype "passive"))
    )
    (net (code "60") (name "Net-(F5-Pad2)") (class "Default")
      (node (ref "F5") (pin "2") (pinfunction "2_2") (pintype "passive"))
      (node (ref "J1") (pin "4") (pinfunction "4_4") (pintype "passive"))
      (node (ref "J2") (pin "4") (pinfunction "4_4") (pintype "passive"))
    )
    (net (code "61") (name "Net-(F6-Pad1)") (class "Default")
      (node (ref "F6") (pin "1") (pinfunction "1_1") (pintype "passive"))
      (node (ref "R5") (pin "1") (pinfunction "1_1") (pintype "passive"))
    )
    (net (code "62") (name "Net-(F7-Pad1)") (class "Default")
      (node (ref "F7") (pin "1") (pinfunction "1_1") (pintype "passive"))
      (node (ref "R6") (pin "1") (pinfunction "1_1") (pintype "passive"))
    )
    (net (code "63") (name "Net-(F7-Pad2)") (class "Default")
      (node (ref "F7") (pin "2") (pinfunction "2_2") (pintype "passive"))
      (node (ref "J1") (pin "6") (pinfunction "6_6") (pintype "passive"))
      (node (ref "J2") (pin "6") (pinfunction "6_6") (pintype "passive"))
    )
    (net (code "64") (name "Net-(J5-Pad1)") (class "Default")
      (node (ref "J5") (pin "1") (pinfunction "1_1") (pintype "passive"))
      (node (ref "X4") (pin "1") (pinfunction "1_1") (pintype "passive"))
    )
    (net (code "65") (name "Net-(J5-Pad2)") (class "Default")
      (node (ref "J5") (pin "2") (pinfunction "2_2") (pintype "passive"))
      (node (ref "X3") (pin "1") (pinfunction "1_1") (pintype "passive"))
    )
    (net (code "66") (name "Net-(Q1-GATE)") (class "Default")
      (node (ref "Q1") (pin "3") (pinfunction "GATE_3") (pintype "passive"))
      (node (ref "Q2") (pin "3") (pinfunction "DRAIN_3") (pintype "passive"))
      (node (ref "R26") (pin "2") (pinfunction "2_2") (pintype "passive"))
    )
    (net (code "67") (name "Net-(U1-VCC)") (class "Default")
      (node (ref "C2") (pin "1") (pinfunction "1_1") (pintype "passive"))
      (node (ref "SW1") (pin "2") (pinfunction "2_2") (pintype "passive"))
      (node (ref "U1") (pin "2") (pinfunction "VCC_2") (pintype "passive"))
    )
    (net (code "68") (name "Net-(U4-VDDCORE{slash}VCAP)") (class "Default")
      (node (ref "C16") (pin "1") (pinfunction "1_1") (pintype "passive"))
      (node (ref "U4") (pin "6") (pinfunction "VDDCORE/VCAP_6") (pintype "passive"))
    )
    (net (code "69") (name "Net-(U6-RS)") (class "Default")
      (node (ref "R15") (pin "2") (pinfunction "2_2") (pintype "passive"))
      (node (ref "U6") (pin "8") (pinfunction "RS_8") (pintype "passive"))
    )
    (net (code "70") (name "unconnected-(F1-Pad3)") (class "Default")
      (node (ref "F1") (pin "3") (pintype "passive"))
    )
    (net (code "71") (name "unconnected-(F1-Pad4)") (class "Default")
      (node (ref "F1") (pin "4") (pintype "passive"))
    )
    (net (code "72") (name "unconnected-(J3-Pad6)") (class "Default")
      (node (ref "J3") (pin "6") (pinfunction "6_6") (pintype "passive"))
    )
    (net (code "73") (name "unconnected-(U2-SO-Pad14)") (class "Default")
      (node (ref "U2") (pin "14") (pinfunction "SO_14") (pintype "passive"))
    )
    (net (code "74") (name "unconnected-(U4-RA5{slash}AN4-Pad7)") (class "Default")
      (node (ref "U4") (pin "7") (pinfunction "RA5/AN4_7") (pintype "passive"))
    )
  )
)
